# Actuator.net
KiCad netlist of a schematic drawn in EAGLE
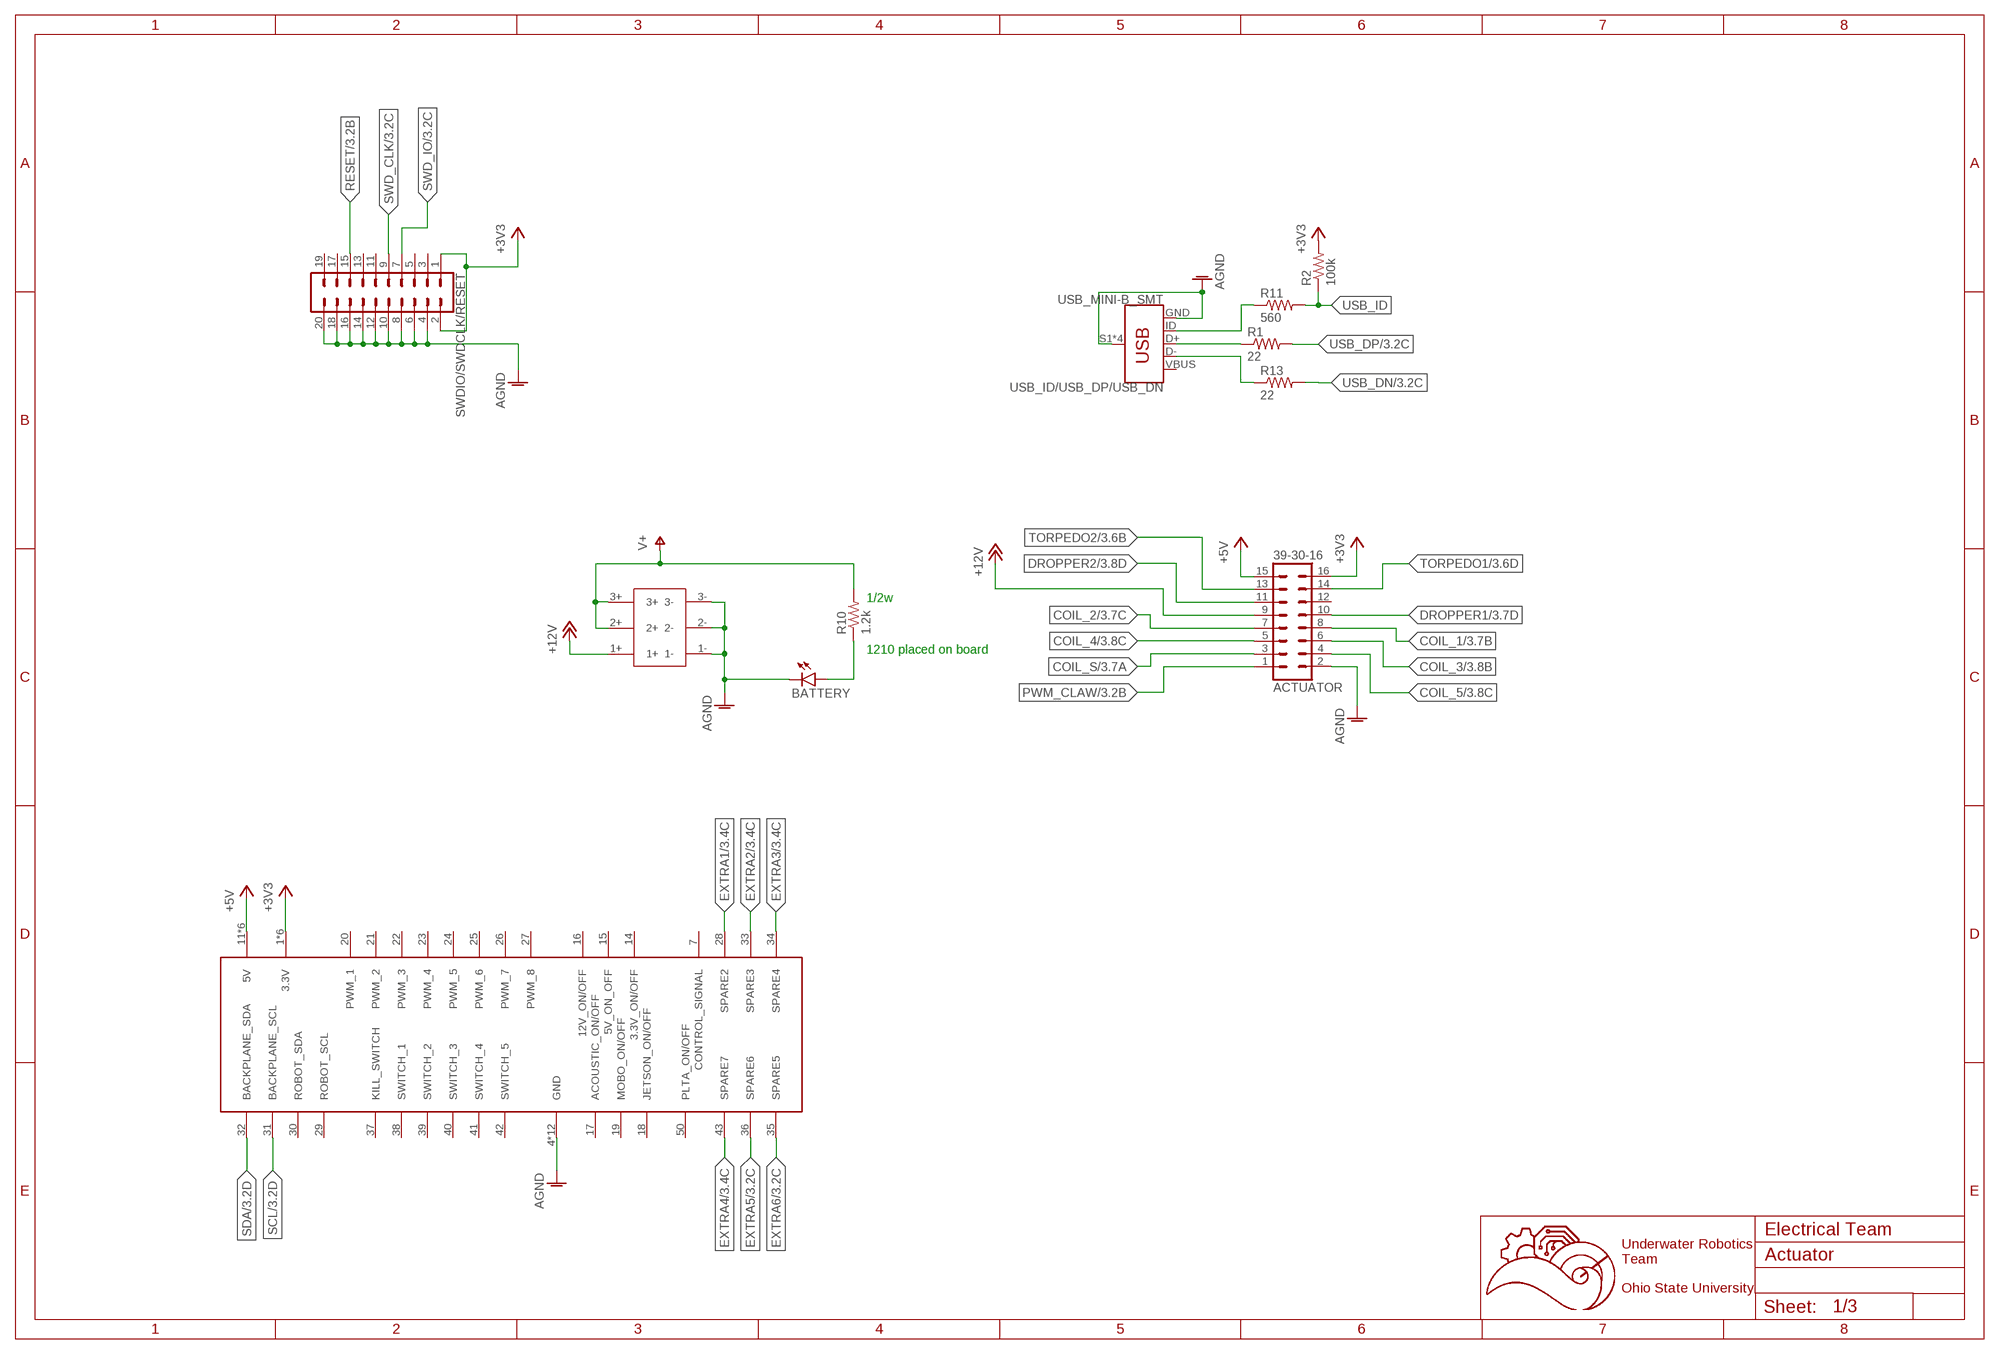
[diagram p0: schematic, sheet 1]
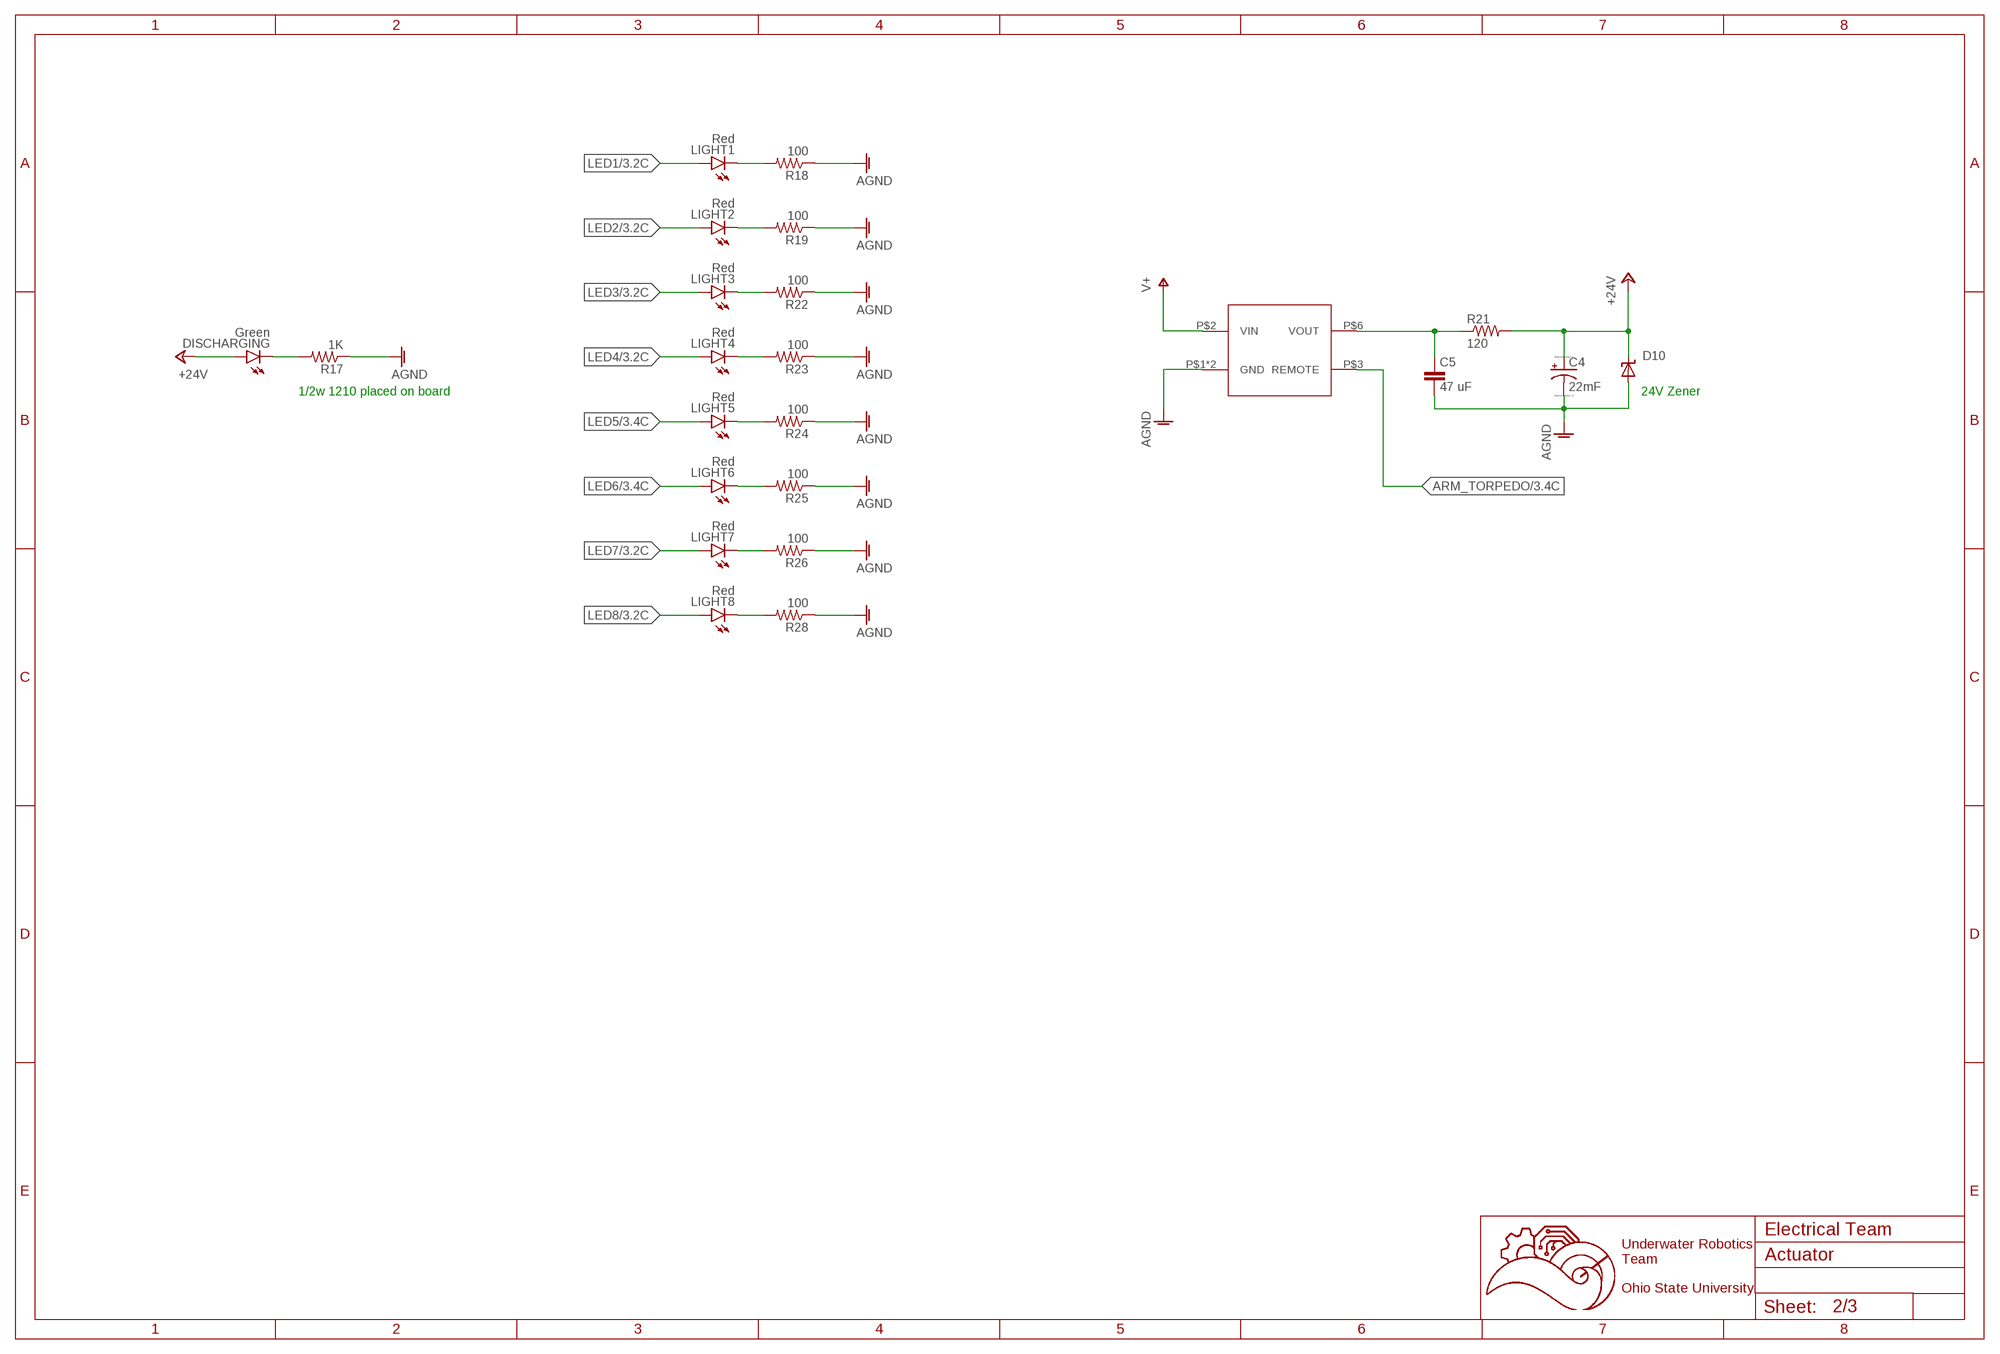
[diagram p1: schematic, sheet 2]
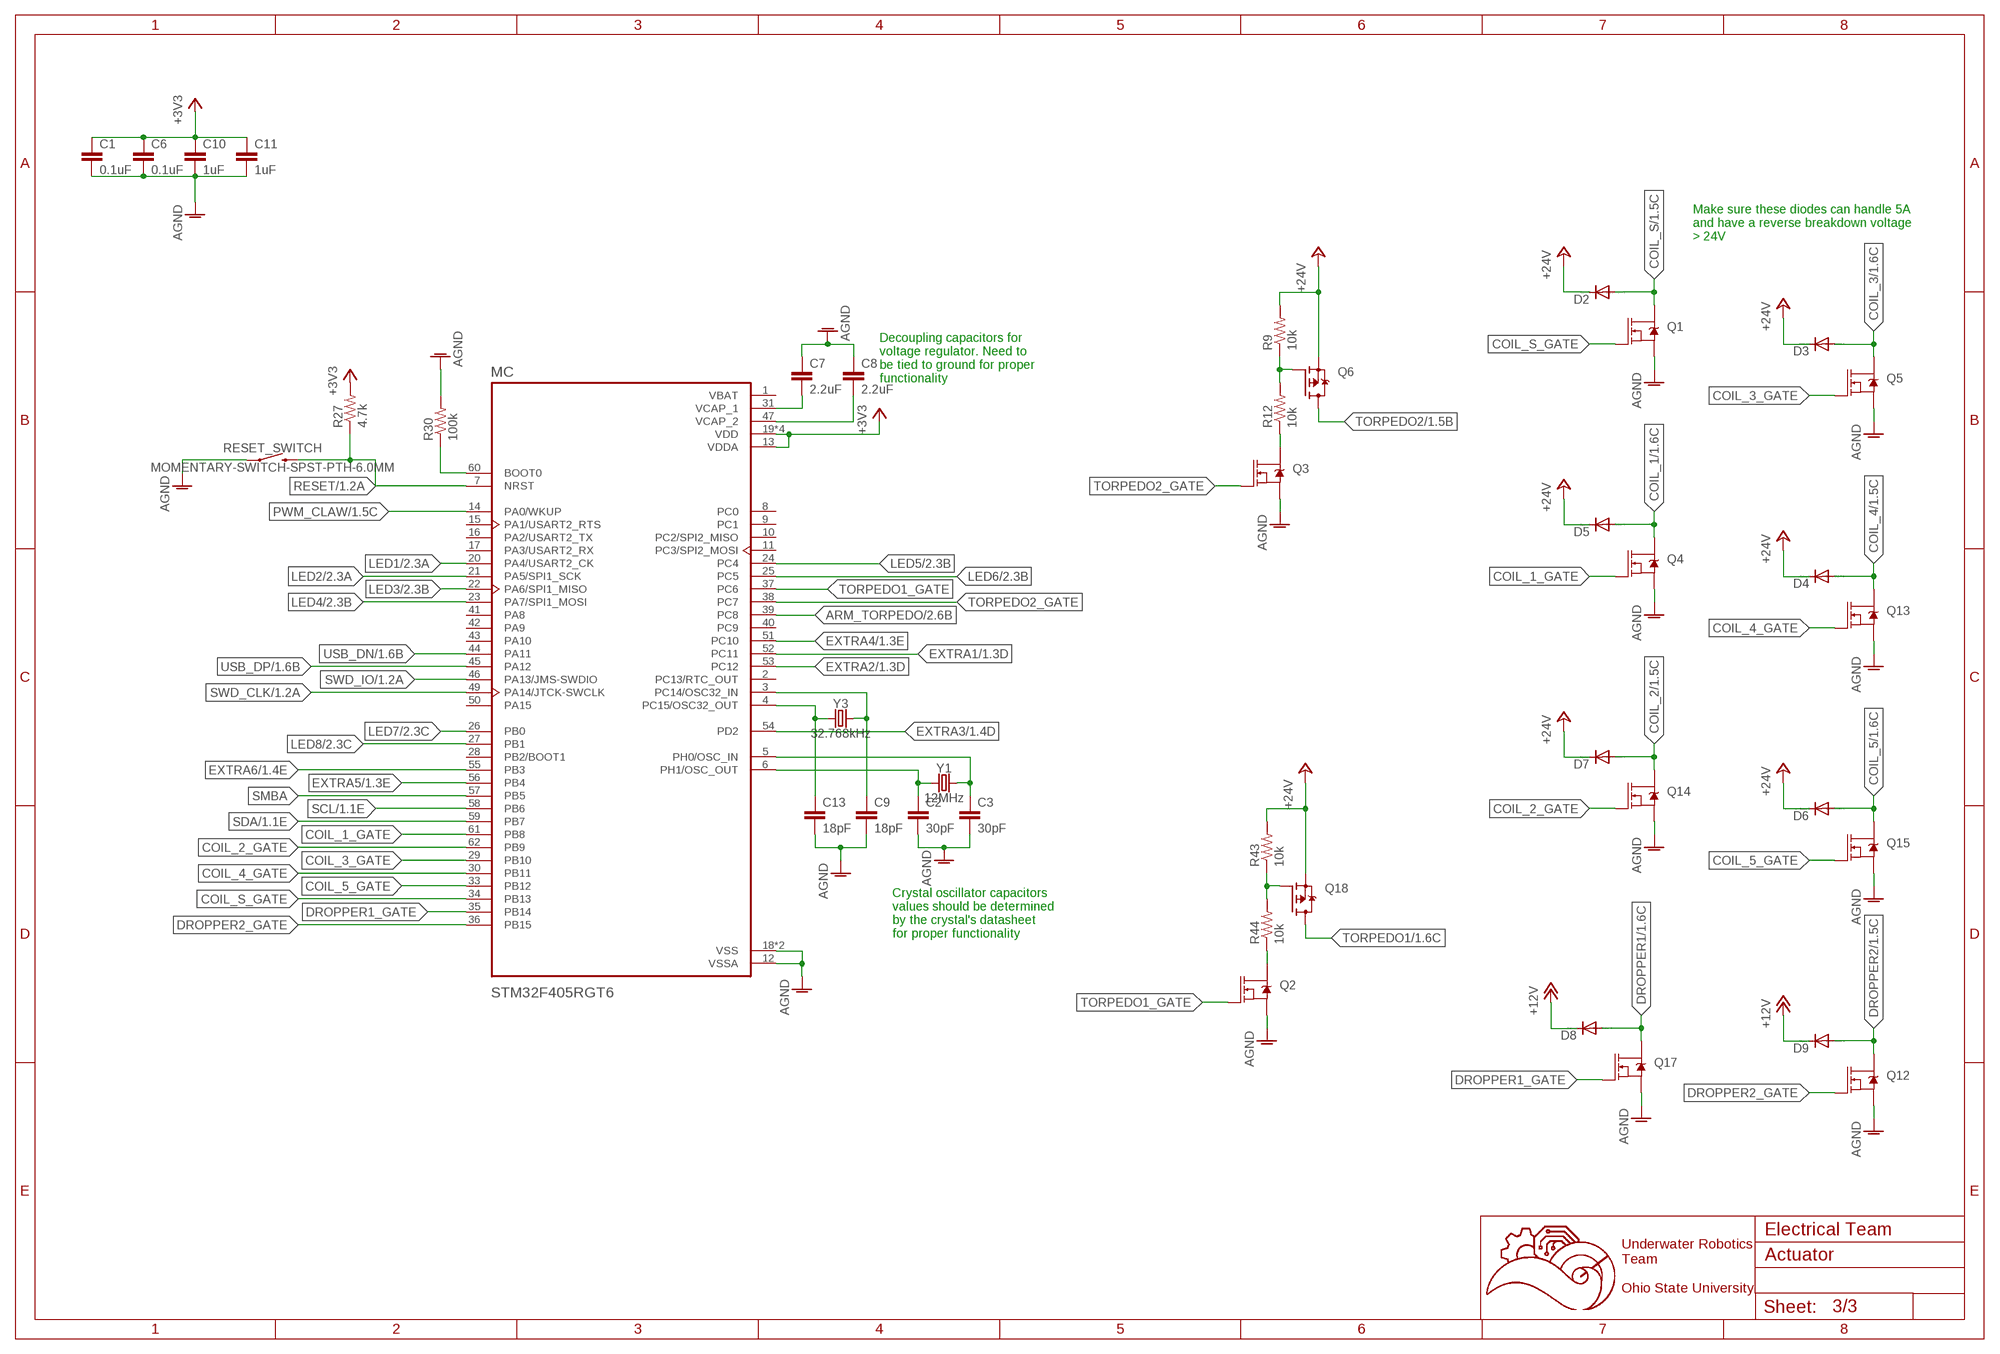
[diagram p2: schematic, sheet 3]

(export (version "E")
  (design (tool "Eeschema 10.0.6"))
  (components
    (comp (ref "C1")
      (value "0.1uF")
      (footprint "eagle-import:C0603")
      (libsource (lib "eagle-import") (part "C-EUC0603"))
    )
    (comp (ref "C2")
      (value "30pF")
      (footprint "eagle-import:C0603")
      (libsource (lib "eagle-import") (part "C-EUC0603"))
    )
    (comp (ref "C3")
      (value "30pF")
      (footprint "eagle-import:C0603")
      (libsource (lib "eagle-import") (part "C-EUC0603"))
    )
    (comp (ref "C6")
      (value "0.1uF")
      (footprint "eagle-import:C0603")
      (libsource (lib "eagle-import") (part "C-EUC0603"))
    )
    (comp (ref "C7")
      (value "2.2uF")
      (footprint "eagle-import:C0603")
      (libsource (lib "eagle-import") (part "C-EUC0603"))
    )
    (comp (ref "C8")
      (value "2.2uF")
      (footprint "eagle-import:C0603")
      (libsource (lib "eagle-import") (part "C-EUC0603"))
    )
    (comp (ref "C9")
      (value "18pF")
      (footprint "eagle-import:C0603")
      (libsource (lib "eagle-import") (part "C-EUC0603"))
    )
    (comp (ref "C10")
      (value "1uF")
      (footprint "eagle-import:C0603")
      (libsource (lib "eagle-import") (part "C-EUC0603"))
    )
    (comp (ref "C11")
      (value "1uF")
      (footprint "eagle-import:C0603")
      (libsource (lib "eagle-import") (part "C-EUC0603"))
    )
    (comp (ref "C13")
      (value "18pF")
      (footprint "eagle-import:C0603")
      (libsource (lib "eagle-import") (part "C-EUC0603"))
    )
    (comp (ref "D2")
      (value "DIODE-SMB")
      (footprint "eagle-import:SMB")
      (libsource (lib "eagle-import") (part "DIODE-SMB"))
    )
    (comp (ref "D3")
      (value "DIODE-SMB")
      (footprint "eagle-import:SMB")
      (libsource (lib "eagle-import") (part "DIODE-SMB"))
    )
    (comp (ref "D4")
      (value "DIODE-SMB")
      (footprint "eagle-import:SMB")
      (libsource (lib "eagle-import") (part "DIODE-SMB"))
    )
    (comp (ref "D5")
      (value "DIODE-SMB")
      (footprint "eagle-import:SMB")
      (libsource (lib "eagle-import") (part "DIODE-SMB"))
    )
    (comp (ref "D6")
      (value "DIODE-SMB")
      (footprint "eagle-import:SMB")
      (libsource (lib "eagle-import") (part "DIODE-SMB"))
    )
    (comp (ref "D7")
      (value "DIODE-SMB")
      (footprint "eagle-import:SMB")
      (libsource (lib "eagle-import") (part "DIODE-SMB"))
    )
    (comp (ref "D8")
      (value "DIODE-SMB")
      (footprint "eagle-import:SMB")
      (libsource (lib "eagle-import") (part "DIODE-SMB"))
    )
    (comp (ref "D9")
      (value "DIODE-SMB")
      (footprint "eagle-import:SMB")
      (libsource (lib "eagle-import") (part "DIODE-SMB"))
    )
    (comp (ref "MC")
      (value "STM32F405RGT6")
      (footprint "eagle-import:QFP50P1200X1200X160-64N")
      (fields (field (name "MF") "STMicroelectronics"))
      (libsource (lib "eagle-import") (part "STM32F405RGT6"))
    )
    (comp (ref "Q1")
      (value "MOSFET-NCH-AO3404A")
      (footprint "eagle-import:SOT23-3")
      (libsource (lib "eagle-import") (part "MOSFET-NCH-AO3404A"))
    )
    (comp (ref "Q2")
      (value "MOSFET-NCH-AO3404A")
      (footprint "eagle-import:SOT23-3")
      (libsource (lib "eagle-import") (part "MOSFET-NCH-AO3404A"))
    )
    (comp (ref "Q3")
      (value "MOSFET-NCH-AO3404A")
      (footprint "eagle-import:SOT23-3")
      (libsource (lib "eagle-import") (part "MOSFET-NCH-AO3404A"))
    )
    (comp (ref "Q4")
      (value "MOSFET-NCH-AO3404A")
      (footprint "eagle-import:SOT23-3")
      (libsource (lib "eagle-import") (part "MOSFET-NCH-AO3404A"))
    )
    (comp (ref "Q5")
      (value "MOSFET-NCH-AO3404A")
      (footprint "eagle-import:SOT23-3")
      (libsource (lib "eagle-import") (part "MOSFET-NCH-AO3404A"))
    )
    (comp (ref "Q6")
      (value "FDD4141TO252")
      (footprint "eagle-import:TO252")
      (libsource (lib "eagle-import") (part "FDD4141TO252"))
    )
    (comp (ref "Q12")
      (value "MOSFET-NCH-AO3404A")
      (footprint "eagle-import:SOT23-3")
      (libsource (lib "eagle-import") (part "MOSFET-NCH-AO3404A"))
    )
    (comp (ref "Q13")
      (value "MOSFET-NCH-AO3404A")
      (footprint "eagle-import:SOT23-3")
      (libsource (lib "eagle-import") (part "MOSFET-NCH-AO3404A"))
    )
    (comp (ref "Q14")
      (value "MOSFET-NCH-AO3404A")
      (footprint "eagle-import:SOT23-3")
      (libsource (lib "eagle-import") (part "MOSFET-NCH-AO3404A"))
    )
    (comp (ref "Q15")
      (value "MOSFET-NCH-AO3404A")
      (footprint "eagle-import:SOT23-3")
      (libsource (lib "eagle-import") (part "MOSFET-NCH-AO3404A"))
    )
    (comp (ref "Q17")
      (value "MOSFET-NCH-AO3404A")
      (footprint "eagle-import:SOT23-3")
      (libsource (lib "eagle-import") (part "MOSFET-NCH-AO3404A"))
    )
    (comp (ref "Q18")
      (value "FDD4141TO252")
      (footprint "eagle-import:TO252")
      (libsource (lib "eagle-import") (part "FDD4141TO252"))
    )
    (comp (ref "R9")
      (value "10k")
      (footprint "eagle-import:R0603")
      (libsource (lib "eagle-import") (part "resistor_348_R-US_R0603"))
    )
    (comp (ref "R12")
      (value "10k")
      (footprint "eagle-import:R0603")
      (libsource (lib "eagle-import") (part "resistor_348_R-US_R0603"))
    )
    (comp (ref "R27")
      (value "4.7k")
      (footprint "eagle-import:R0603")
      (libsource (lib "eagle-import") (part "R-US_R0603"))
    )
    (comp (ref "R30")
      (value "100k")
      (footprint "eagle-import:R0603")
      (libsource (lib "eagle-import") (part "R-US_R0603"))
    )
    (comp (ref "R43")
      (value "10k")
      (footprint "eagle-import:R0603")
      (libsource (lib "eagle-import") (part "resistor_348_R-US_R0603"))
    )
    (comp (ref "R44")
      (value "10k")
      (footprint "eagle-import:R0603")
      (libsource (lib "eagle-import") (part "resistor_348_R-US_R0603"))
    )
    (comp (ref "RESET_SWITCH")
      (value "MOMENTARY-SWITCH-SPST-PTH-6.0MM")
      (footprint "eagle-import:TACTILE_SWITCH_PTH_6.0MM")
      (libsource (lib "eagle-import") (part "MOMENTARY-SWITCH-SPST-PTH-6.0MM"))
    )
    (comp (ref "Y1")
      (value "12MHz")
      (footprint "eagle-import:HC49US")
      (libsource (lib "eagle-import") (part "CRYSTAL-16MHZPTH-HC49US"))
    )
    (comp (ref "Y3")
      (value "32.768kHz")
      (footprint "eagle-import:CRYSTAL-SMD-3.2X1.5MM")
      (libsource (lib "eagle-import") (part "CRYSTAL-32.768KHZSMD-3.2X1.5"))
    )
    (comp (ref "C4")
      (value "22mF")
      (footprint "eagle-import:EB30D")
      (libsource (lib "eagle-import") (part "CPOL-USE10-30"))
    )
    (comp (ref "C5")
      (value "47 uF")
      (footprint "eagle-import:C0603")
      (libsource (lib "eagle-import") (part "C-EUC0603"))
    )
    (comp (ref "D10")
      (value "SUPPRESSOR-SMBJ")
      (footprint "eagle-import:SMBJ")
      (libsource (lib "eagle-import") (part "SUPPRESSOR-SMBJ"))
    )
    (comp (ref "DISCHARGING")
      (value "Green")
      (footprint "eagle-import:CHIPLED_0603")
      (libsource (lib "eagle-import") (part "LEDCHIPLED_0603"))
    )
    (comp (ref "LIGHT1")
      (value "Red")
      (footprint "eagle-import:CHIPLED_0603")
      (libsource (lib "eagle-import") (part "LEDCHIPLED_0603"))
    )
    (comp (ref "LIGHT2")
      (value "Red")
      (footprint "eagle-import:CHIPLED_0603")
      (libsource (lib "eagle-import") (part "LEDCHIPLED_0603"))
    )
    (comp (ref "LIGHT3")
      (value "Red")
      (footprint "eagle-import:CHIPLED_0603")
      (libsource (lib "eagle-import") (part "LEDCHIPLED_0603"))
    )
    (comp (ref "LIGHT4")
      (value "Red")
      (footprint "eagle-import:CHIPLED_0603")
      (libsource (lib "eagle-import") (part "LEDCHIPLED_0603"))
    )
    (comp (ref "LIGHT5")
      (value "Red")
      (footprint "eagle-import:CHIPLED_0603")
      (libsource (lib "eagle-import") (part "LEDCHIPLED_0603"))
    )
    (comp (ref "LIGHT6")
      (value "Red")
      (footprint "eagle-import:CHIPLED_0603")
      (libsource (lib "eagle-import") (part "LEDCHIPLED_0603"))
    )
    (comp (ref "LIGHT7")
      (value "Red")
      (footprint "eagle-import:CHIPLED_0603")
      (libsource (lib "eagle-import") (part "LEDCHIPLED_0603"))
    )
    (comp (ref "LIGHT8")
      (value "Red")
      (footprint "eagle-import:CHIPLED_0603")
      (libsource (lib "eagle-import") (part "LEDCHIPLED_0603"))
    )
    (comp (ref "R17")
      (value "1K")
      (footprint "eagle-import:R1210")
      (libsource (lib "eagle-import") (part "R-US_R1210"))
    )
    (comp (ref "R18")
      (value "100")
      (footprint "eagle-import:R0603")
      (libsource (lib "eagle-import") (part "R-US_R0603"))
    )
    (comp (ref "R19")
      (value "100")
      (footprint "eagle-import:R0603")
      (libsource (lib "eagle-import") (part "R-US_R0603"))
    )
    (comp (ref "R21")
      (value "120")
      (footprint "eagle-import:R6332W")
      (libsource (lib "eagle-import") (part "resistor_348_R-US_R6332W"))
    )
    (comp (ref "R22")
      (value "100")
      (footprint "eagle-import:R0603")
      (libsource (lib "eagle-import") (part "R-US_R0603"))
    )
    (comp (ref "R23")
      (value "100")
      (footprint "eagle-import:R0603")
      (libsource (lib "eagle-import") (part "R-US_R0603"))
    )
    (comp (ref "R24")
      (value "100")
      (footprint "eagle-import:R0603")
      (libsource (lib "eagle-import") (part "R-US_R0603"))
    )
    (comp (ref "R25")
      (value "100")
      (footprint "eagle-import:R0603")
      (libsource (lib "eagle-import") (part "R-US_R0603"))
    )
    (comp (ref "R26")
      (value "100")
      (footprint "eagle-import:R0603")
      (libsource (lib "eagle-import") (part "R-US_R0603"))
    )
    (comp (ref "R28")
      (value "100")
      (footprint "eagle-import:R0603")
      (libsource (lib "eagle-import") (part "R-US_R0603"))
    )
    (comp (ref "U$6")
      (value "TMR6-2415")
      (footprint "eagle-import:TMR6-2415")
      (libsource (lib "eagle-import") (part "TMR6-2415"))
    )
    (comp (ref "ACTUATOR")
      (value "39-30-16")
      (footprint "eagle-import:39-30-_16_")
      (libsource (lib "eagle-import") (part "39-30-?16?"))
    )
    (comp (ref "BATTERY")
      (value "LEDCHIPLED_0603")
      (footprint "eagle-import:CHIPLED_0603")
      (libsource (lib "eagle-import") (part "LEDCHIPLED_0603"))
    )
    (comp (ref "R1")
      (value "22")
      (footprint "eagle-import:R0603")
      (libsource (lib "eagle-import") (part "R-US_R0603"))
    )
    (comp (ref "R2")
      (value "100k")
      (footprint "eagle-import:R0603")
      (libsource (lib "eagle-import") (part "R-US_R0603"))
    )
    (comp (ref "R10")
      (value "1.2k")
      (footprint "eagle-import:R1210")
      (libsource (lib "eagle-import") (part "R-US_R1210"))
    )
    (comp (ref "R11")
      (value "560")
      (footprint "eagle-import:R0603")
      (libsource (lib "eagle-import") (part "R-US_R0603"))
    )
    (comp (ref "R13")
      (value "22")
      (footprint "eagle-import:R0603")
      (libsource (lib "eagle-import") (part "R-US_R0603"))
    )
    (comp (ref "SWDIO/SWDCLK/RESET")
      (value "CONN_10X2")
      (footprint "eagle-import:2X10")
      (libsource (lib "eagle-import") (part "CONN_10X2"))
    )
    (comp (ref "U$1")
      (value "5530843-EDGE")
      (footprint "eagle-import:5530843-6-BOARDFINGERS")
      (libsource (lib "eagle-import") (part "5530843-EDGE"))
    )
    (comp (ref "U$3")
      (value "6PIN-VERT")
      (footprint "eagle-import:6PIN_VERT")
      (libsource (lib "eagle-import") (part "6PIN-VERT"))
    )
    (comp (ref "USB_ID/USB_DP/USB_DN")
      (value "USB_MINI-B_SMT")
      (footprint "eagle-import:USB-MINIB")
      (libsource (lib "eagle-import") (part "USB_MINI-B_SMT"))
    )
  )
  (nets
    (net (code "1") (name "+3V3") (class "Default")
      (node (ref "ACTUATOR") (pin "16") (pinfunction "16_16") (pintype "passive"))
      (node (ref "C1") (pin "1") (pinfunction "1_1") (pintype "passive"))
      (node (ref "C10") (pin "1") (pinfunction "1_1") (pintype "passive"))
      (node (ref "C11") (pin "1") (pinfunction "1_1") (pintype "passive"))
      (node (ref "C6") (pin "1") (pinfunction "1_1") (pintype "passive"))
      (node (ref "MC") (pin "13") (pinfunction "VDDA_13") (pintype "power_in"))
      (node (ref "MC") (pin "19") (pinfunction "VDD_19") (pintype "power_in"))
      (node (ref "MC") (pin "32") (pinfunction "VDD_32") (pintype "power_in"))
      (node (ref "MC") (pin "48") (pinfunction "VDD_48") (pintype "power_in"))
      (node (ref "MC") (pin "64") (pinfunction "VDD_64") (pintype "power_in"))
      (node (ref "R2") (pin "2") (pinfunction "2_2") (pintype "passive"))
      (node (ref "R27") (pin "2") (pinfunction "2_2") (pintype "passive"))
      (node (ref "SWDIO/SWDCLK/RESET") (pin "1") (pinfunction "1_1") (pintype "passive"))
      (node (ref "SWDIO/SWDCLK/RESET") (pin "2") (pinfunction "2_2") (pintype "passive"))
      (node (ref "U$1") (pin "1") (pinfunction "3.3V_1") (pintype "bidirectional"))
      (node (ref "U$1") (pin "2") (pinfunction "3.3V_2") (pintype "bidirectional"))
      (node (ref "U$1") (pin "3") (pinfunction "3.3V_3") (pintype "bidirectional"))
      (node (ref "U$1") (pin "54") (pinfunction "3.3V_54") (pintype "bidirectional"))
      (node (ref "U$1") (pin "55") (pinfunction "3.3V_55") (pintype "bidirectional"))
      (node (ref "U$1") (pin "56") (pinfunction "3.3V_56") (pintype "bidirectional"))
    )
    (net (code "2") (name "+5V") (class "Default")
      (node (ref "ACTUATOR") (pin "15") (pinfunction "15_15") (pintype "passive"))
      (node (ref "U$1") (pin "11") (pinfunction "5V_11") (pintype "bidirectional"))
      (node (ref "U$1") (pin "12") (pinfunction "5V_12") (pintype "bidirectional"))
      (node (ref "U$1") (pin "13") (pinfunction "5V_13") (pintype "bidirectional"))
      (node (ref "U$1") (pin "44") (pinfunction "5V_44") (pintype "bidirectional"))
      (node (ref "U$1") (pin "45") (pinfunction "5V_45") (pintype "bidirectional"))
      (node (ref "U$1") (pin "46") (pinfunction "5V_46") (pintype "bidirectional"))
    )
    (net (code "3") (name "+12V") (class "Default")
      (node (ref "ACTUATOR") (pin "9") (pinfunction "9_9") (pintype "passive"))
      (node (ref "D8") (pin "C") (pinfunction "C_C") (pintype "passive"))
      (node (ref "D9") (pin "C") (pinfunction "C_C") (pintype "passive"))
      (node (ref "U$3") (pin "1+") (pinfunction "1+_1+") (pintype "bidirectional"))
    )
    (net (code "4") (name "+24V") (class "Default")
      (node (ref "C4") (pin "+") (pinfunction "+_+") (pintype "passive"))
      (node (ref "D10") (pin "C") (pinfunction "C_C") (pintype "passive"))
      (node (ref "D2") (pin "C") (pinfunction "C_C") (pintype "passive"))
      (node (ref "D3") (pin "C") (pinfunction "C_C") (pintype "passive"))
      (node (ref "D4") (pin "C") (pinfunction "C_C") (pintype "passive"))
      (node (ref "D5") (pin "C") (pinfunction "C_C") (pintype "passive"))
      (node (ref "D6") (pin "C") (pinfunction "C_C") (pintype "passive"))
      (node (ref "D7") (pin "C") (pinfunction "C_C") (pintype "passive"))
      (node (ref "DISCHARGING") (pin "A") (pinfunction "A_A") (pintype "passive"))
      (node (ref "Q18") (pin "2") (pinfunction "S_2") (pintype "passive"))
      (node (ref "Q6") (pin "2") (pinfunction "S_2") (pintype "passive"))
      (node (ref "R21") (pin "2") (pinfunction "2_2") (pintype "passive"))
      (node (ref "R43") (pin "2") (pinfunction "2_2") (pintype "passive"))
      (node (ref "R9") (pin "2") (pinfunction "2_2") (pintype "passive"))
    )
    (net (code "5") (name "AGND") (class "Default")
      (node (ref "ACTUATOR") (pin "2") (pinfunction "2_2") (pintype "passive"))
      (node (ref "BATTERY") (pin "C") (pinfunction "C_C") (pintype "passive"))
      (node (ref "C1") (pin "2") (pinfunction "2_2") (pintype "passive"))
      (node (ref "C10") (pin "2") (pinfunction "2_2") (pintype "passive"))
      (node (ref "C11") (pin "2") (pinfunction "2_2") (pintype "passive"))
      (node (ref "C13") (pin "2") (pinfunction "2_2") (pintype "passive"))
      (node (ref "C2") (pin "2") (pinfunction "2_2") (pintype "passive"))
      (node (ref "C3") (pin "2") (pinfunction "2_2") (pintype "passive"))
      (node (ref "C4") (pin "-") (pinfunction "-_-") (pintype "passive"))
      (node (ref "C5") (pin "2") (pinfunction "2_2") (pintype "passive"))
      (node (ref "C6") (pin "2") (pinfunction "2_2") (pintype "passive"))
      (node (ref "C7") (pin "1") (pinfunction "1_1") (pintype "passive"))
      (node (ref "C8") (pin "1") (pinfunction "1_1") (pintype "passive"))
      (node (ref "C9") (pin "2") (pinfunction "2_2") (pintype "passive"))
      (node (ref "D10") (pin "A") (pinfunction "A_A") (pintype "passive"))
      (node (ref "MC") (pin "12") (pinfunction "VSSA_12") (pintype "power_in"))
      (node (ref "MC") (pin "18") (pinfunction "VSS_18") (pintype "power_in"))
      (node (ref "MC") (pin "63") (pinfunction "VSS_63") (pintype "power_in"))
      (node (ref "Q1") (pin "2") (pinfunction "S_2") (pintype "bidirectional"))
      (node (ref "Q12") (pin "2") (pinfunction "S_2") (pintype "bidirectional"))
      (node (ref "Q13") (pin "2") (pinfunction "S_2") (pintype "bidirectional"))
      (node (ref "Q14") (pin "2") (pinfunction "S_2") (pintype "bidirectional"))
      (node (ref "Q15") (pin "2") (pinfunction "S_2") (pintype "bidirectional"))
      (node (ref "Q17") (pin "2") (pinfunction "S_2") (pintype "bidirectional"))
      (node (ref "Q2") (pin "2") (pinfunction "S_2") (pintype "bidirectional"))
      (node (ref "Q3") (pin "2") (pinfunction "S_2") (pintype "bidirectional"))
      (node (ref "Q4") (pin "2") (pinfunction "S_2") (pintype "bidirectional"))
      (node (ref "Q5") (pin "2") (pinfunction "S_2") (pintype "bidirectional"))
      (node (ref "R17") (pin "1") (pinfunction "1_1") (pintype "passive"))
      (node (ref "R18") (pin "1") (pinfunction "1_1") (pintype "passive"))
      (node (ref "R19") (pin "1") (pinfunction "1_1") (pintype "passive"))
      (node (ref "R22") (pin "1") (pinfunction "1_1") (pintype "passive"))
      (node (ref "R23") (pin "1") (pinfunction "1_1") (pintype "passive"))
      (node (ref "R24") (pin "1") (pinfunction "1_1") (pintype "passive"))
      (node (ref "R25") (pin "1") (pinfunction "1_1") (pintype "passive"))
      (node (ref "R26") (pin "1") (pinfunction "1_1") (pintype "passive"))
      (node (ref "R28") (pin "1") (pinfunction "1_1") (pintype "passive"))
      (node (ref "R30") (pin "2") (pinfunction "2_2") (pintype "passive"))
      (node (ref "RESET_SWITCH") (pin "1") (pinfunction "1_1") (pintype "passive"))
      (node (ref "SWDIO/SWDCLK/RESET") (pin "10") (pinfunction "10_10") (pintype "passive"))
      (node (ref "SWDIO/SWDCLK/RESET") (pin "12") (pinfunction "12_12") (pintype "passive"))
      (node (ref "SWDIO/SWDCLK/RESET") (pin "14") (pinfunction "14_14") (pintype "passive"))
      (node (ref "SWDIO/SWDCLK/RESET") (pin "16") (pinfunction "16_16") (pintype "passive"))
      (node (ref "SWDIO/SWDCLK/RESET") (pin "18") (pinfunction "18_18") (pintype "passive"))
      (node (ref "SWDIO/SWDCLK/RESET") (pin "20") (pinfunction "20_20") (pintype "passive"))
      (node (ref "SWDIO/SWDCLK/RESET") (pin "4") (pinfunction "4_4") (pintype "passive"))
      (node (ref "SWDIO/SWDCLK/RESET") (pin "6") (pinfunction "6_6") (pintype "passive"))
      (node (ref "SWDIO/SWDCLK/RESET") (pin "8") (pinfunction "8_8") (pintype "passive"))
      (node (ref "U$1") (pin "10") (pinfunction "GND_10") (pintype "bidirectional"))
      (node (ref "U$1") (pin "4") (pinfunction "GND_4") (pintype "bidirectional"))
      (node (ref "U$1") (pin "47") (pinfunction "GND_47") (pintype "bidirectional"))
      (node (ref "U$1") (pin "48") (pinfunction "GND_48") (pintype "bidirectional"))
      (node (ref "U$1") (pin "49") (pinfunction "GND_49") (pintype "bidirectional"))
      (node (ref "U$1") (pin "5") (pinfunction "GND_5") (pintype "bidirectional"))
      (node (ref "U$1") (pin "51") (pinfunction "GND_51") (pintype "bidirectional"))
      (node (ref "U$1") (pin "52") (pinfunction "GND_52") (pintype "bidirectional"))
      (node (ref "U$1") (pin "53") (pinfunction "GND_53") (pintype "bidirectional"))
      (node (ref "U$1") (pin "6") (pinfunction "GND_6") (pintype "bidirectional"))
      (node (ref "U$1") (pin "8") (pinfunction "GND_8") (pintype "bidirectional"))
      (node (ref "U$1") (pin "9") (pinfunction "GND_9") (pintype "bidirectional"))
      (node (ref "U$3") (pin "1-") (pinfunction "1-_1-") (pintype "bidirectional"))
      (node (ref "U$3") (pin "2-") (pinfunction "2-_2-") (pintype "bidirectional"))
      (node (ref "U$3") (pin "3-") (pinfunction "3-_3-") (pintype "bidirectional"))
      (node (ref "U$6") (pin "P$1") (pinfunction "GND_P$1") (pintype "bidirectional"))
      (node (ref "U$6") (pin "P$7") (pinfunction "GND_P$7") (pintype "bidirectional"))
      (node (ref "USB_ID/USB_DP/USB_DN") (pin "GND") (pinfunction "GND_GND") (pintype "power_in"))
      (node (ref "USB_ID/USB_DP/USB_DN") (pin "S1") (pinfunction "SHIELD_S1") (pintype "bidirectional"))
      (node (ref "USB_ID/USB_DP/USB_DN") (pin "S2") (pinfunction "SHIELD_S2") (pintype "bidirectional"))
      (node (ref "USB_ID/USB_DP/USB_DN") (pin "S3") (pinfunction "SHIELD_S3") (pintype "bidirectional"))
      (node (ref "USB_ID/USB_DP/USB_DN") (pin "S4") (pinfunction "SHIELD_S4") (pintype "bidirectional"))
    )
    (net (code "6") (name "ARM_TORPEDO") (class "Default")
      (node (ref "MC") (pin "39") (pinfunction "PC8_39") (pintype "bidirectional"))
      (node (ref "U$6") (pin "P$3") (pinfunction "REMOTE_P$3") (pintype "bidirectional"))
    )
    (net (code "7") (name "COIL_1") (class "Default")
      (node (ref "ACTUATOR") (pin "8") (pinfunction "8_8") (pintype "passive"))
      (node (ref "D5") (pin "A") (pinfunction "A_A") (pintype "passive"))
      (node (ref "Q4") (pin "3") (pinfunction "D_3") (pintype "bidirectional"))
    )
    (net (code "8") (name "COIL_1_GATE") (class "Default")
      (node (ref "MC") (pin "61") (pinfunction "PB8_61") (pintype "bidirectional"))
      (node (ref "Q4") (pin "1") (pinfunction "G_1") (pintype "bidirectional"))
    )
    (net (code "9") (name "COIL_2") (class "Default")
      (node (ref "ACTUATOR") (pin "7") (pinfunction "7_7") (pintype "passive"))
      (node (ref "D7") (pin "A") (pinfunction "A_A") (pintype "passive"))
      (node (ref "Q14") (pin "3") (pinfunction "D_3") (pintype "bidirectional"))
    )
    (net (code "10") (name "COIL_2_GATE") (class "Default")
      (node (ref "MC") (pin "62") (pinfunction "PB9_62") (pintype "bidirectional"))
      (node (ref "Q14") (pin "1") (pinfunction "G_1") (pintype "bidirectional"))
    )
    (net (code "11") (name "COIL_3") (class "Default")
      (node (ref "ACTUATOR") (pin "6") (pinfunction "6_6") (pintype "passive"))
      (node (ref "D3") (pin "A") (pinfunction "A_A") (pintype "passive"))
      (node (ref "Q5") (pin "3") (pinfunction "D_3") (pintype "bidirectional"))
    )
    (net (code "12") (name "COIL_3_GATE") (class "Default")
      (node (ref "MC") (pin "29") (pinfunction "PB10_29") (pintype "bidirectional"))
      (node (ref "Q5") (pin "1") (pinfunction "G_1") (pintype "bidirectional"))
    )
    (net (code "13") (name "COIL_4") (class "Default")
      (node (ref "ACTUATOR") (pin "5") (pinfunction "5_5") (pintype "passive"))
      (node (ref "D4") (pin "A") (pinfunction "A_A") (pintype "passive"))
      (node (ref "Q13") (pin "3") (pinfunction "D_3") (pintype "bidirectional"))
    )
    (net (code "14") (name "COIL_4_GATE") (class "Default")
      (node (ref "MC") (pin "30") (pinfunction "PB11_30") (pintype "bidirectional"))
      (node (ref "Q13") (pin "1") (pinfunction "G_1") (pintype "bidirectional"))
    )
    (net (code "15") (name "COIL_5") (class "Default")
      (node (ref "ACTUATOR") (pin "4") (pinfunction "4_4") (pintype "passive"))
      (node (ref "D6") (pin "A") (pinfunction "A_A") (pintype "passive"))
      (node (ref "Q15") (pin "3") (pinfunction "D_3") (pintype "bidirectional"))
    )
    (net (code "16") (name "COIL_5_GATE") (class "Default")
      (node (ref "MC") (pin "33") (pinfunction "PB12_33") (pintype "bidirectional"))
      (node (ref "Q15") (pin "1") (pinfunction "G_1") (pintype "bidirectional"))
    )
    (net (code "17") (name "COIL_S") (class "Default")
      (node (ref "ACTUATOR") (pin "3") (pinfunction "3_3") (pintype "passive"))
      (node (ref "D2") (pin "A") (pinfunction "A_A") (pintype "passive"))
      (node (ref "Q1") (pin "3") (pinfunction "D_3") (pintype "bidirectional"))
    )
    (net (code "18") (name "COIL_S_GATE") (class "Default")
      (node (ref "MC") (pin "34") (pinfunction "PB13_34") (pintype "bidirectional"))
      (node (ref "Q1") (pin "1") (pinfunction "G_1") (pintype "bidirectional"))
    )
    (net (code "19") (name "DROPPER1") (class "Default")
      (node (ref "ACTUATOR") (pin "10") (pinfunction "10_10") (pintype "passive"))
      (node (ref "D8") (pin "A") (pinfunction "A_A") (pintype "passive"))
      (node (ref "Q17") (pin "3") (pinfunction "D_3") (pintype "bidirectional"))
    )
    (net (code "20") (name "DROPPER1_GATE") (class "Default")
      (node (ref "MC") (pin "35") (pinfunction "PB14_35") (pintype "bidirectional"))
      (node (ref "Q17") (pin "1") (pinfunction "G_1") (pintype "bidirectional"))
    )
    (net (code "21") (name "DROPPER2") (class "Default")
      (node (ref "ACTUATOR") (pin "11") (pinfunction "11_11") (pintype "passive"))
      (node (ref "D9") (pin "A") (pinfunction "A_A") (pintype "passive"))
      (node (ref "Q12") (pin "3") (pinfunction "D_3") (pintype "bidirectional"))
    )
    (net (code "22") (name "DROPPER2_GATE") (class "Default")
      (node (ref "MC") (pin "36") (pinfunction "PB15_36") (pintype "bidirectional"))
      (node (ref "Q12") (pin "1") (pinfunction "G_1") (pintype "bidirectional"))
    )
    (net (code "23") (name "EXTRA1") (class "Default")
      (node (ref "MC") (pin "52") (pinfunction "PC11_52") (pintype "bidirectional"))
      (node (ref "U$1") (pin "28") (pinfunction "SPARE2_28") (pintype "bidirectional"))
    )
    (net (code "24") (name "EXTRA2") (class "Default")
      (node (ref "MC") (pin "53") (pinfunction "PC12_53") (pintype "bidirectional"))
      (node (ref "U$1") (pin "33") (pinfunction "SPARE3_33") (pintype "bidirectional"))
    )
    (net (code "25") (name "EXTRA3") (class "Default")
      (node (ref "MC") (pin "54") (pinfunction "PD2_54") (pintype "bidirectional"))
      (node (ref "U$1") (pin "34") (pinfunction "SPARE4_34") (pintype "bidirectional"))
    )
    (net (code "26") (name "EXTRA4") (class "Default")
      (node (ref "MC") (pin "51") (pinfunction "PC10_51") (pintype "bidirectional"))
      (node (ref "U$1") (pin "43") (pinfunction "SPARE7_43") (pintype "bidirectional"))
    )
    (net (code "27") (name "EXTRA5") (class "Default")
      (node (ref "MC") (pin "56") (pinfunction "PB4_56") (pintype "bidirectional"))
      (node (ref "U$1") (pin "36") (pinfunction "SPARE6_36") (pintype "bidirectional"))
    )
    (net (code "28") (name "EXTRA6") (class "Default")
      (node (ref "MC") (pin "55") (pinfunction "PB3_55") (pintype "bidirectional"))
      (node (ref "U$1") (pin "35") (pinfunction "SPARE5_35") (pintype "bidirectional"))
    )
    (net (code "29") (name "LED1") (class "Default")
      (node (ref "LIGHT1") (pin "A") (pinfunction "A_A") (pintype "passive"))
      (node (ref "MC") (pin "20") (pinfunction "PA4/USART2_CK_20") (pintype "bidirectional"))
    )
    (net (code "30") (name "LED2") (class "Default")
      (node (ref "LIGHT2") (pin "A") (pinfunction "A_A") (pintype "passive"))
      (node (ref "MC") (pin "21") (pinfunction "PA5/SPI1_SCK_21") (pintype "bidirectional"))
    )
    (net (code "31") (name "LED3") (class "Default")
      (node (ref "LIGHT3") (pin "A") (pinfunction "A_A") (pintype "passive"))
      (node (ref "MC") (pin "22") (pinfunction "PA6/SPI1_MISO_22") (pintype "bidirectional"))
    )
    (net (code "32") (name "LED4") (class "Default")
      (node (ref "LIGHT4") (pin "A") (pinfunction "A_A") (pintype "passive"))
      (node (ref "MC") (pin "23") (pinfunction "PA7/SPI1_MOSI_23") (pintype "bidirectional"))
    )
    (net (code "33") (name "LED5") (class "Default")
      (node (ref "LIGHT5") (pin "A") (pinfunction "A_A") (pintype "passive"))
      (node (ref "MC") (pin "24") (pinfunction "PC4_24") (pintype "bidirectional"))
    )
    (net (code "34") (name "LED6") (class "Default")
      (node (ref "LIGHT6") (pin "A") (pinfunction "A_A") (pintype "passive"))
      (node (ref "MC") (pin "25") (pinfunction "PC5_25") (pintype "bidirectional"))
    )
    (net (code "35") (name "LED7") (class "Default")
      (node (ref "LIGHT7") (pin "A") (pinfunction "A_A") (pintype "passive"))
      (node (ref "MC") (pin "26") (pinfunction "PB0_26") (pintype "bidirectional"))
    )
    (net (code "36") (name "LED8") (class "Default")
      (node (ref "LIGHT8") (pin "A") (pinfunction "A_A") (pintype "passive"))
      (node (ref "MC") (pin "27") (pinfunction "PB1_27") (pintype "bidirectional"))
    )
    (net (code "37") (name "Net-(BATTERY-PadA)") (class "Default")
      (node (ref "BATTERY") (pin "A") (pinfunction "A_A") (pintype "passive"))
      (node (ref "R10") (pin "1") (pinfunction "1_1") (pintype "passive"))
    )
    (net (code "38") (name "Net-(DISCHARGING-PadC)") (class "Default")
      (node (ref "DISCHARGING") (pin "C") (pinfunction "C_C") (pintype "passive"))
      (node (ref "R17") (pin "2") (pinfunction "2_2") (pintype "passive"))
    )
    (net (code "39") (name "Net-(LIGHT1-PadC)") (class "Default")
      (node (ref "LIGHT1") (pin "C") (pinfunction "C_C") (pintype "passive"))
      (node (ref "R18") (pin "2") (pinfunction "2_2") (pintype "passive"))
    )
    (net (code "40") (name "Net-(LIGHT2-PadC)") (class "Default")
      (node (ref "LIGHT2") (pin "C") (pinfunction "C_C") (pintype "passive"))
      (node (ref "R19") (pin "2") (pinfunction "2_2") (pintype "passive"))
    )
    (net (code "41") (name "Net-(LIGHT3-PadC)") (class "Default")
      (node (ref "LIGHT3") (pin "C") (pinfunction "C_C") (pintype "passive"))
      (node (ref "R22") (pin "2") (pinfunction "2_2") (pintype "passive"))
    )
    (net (code "42") (name "Net-(LIGHT4-PadC)") (class "Default")
      (node (ref "LIGHT4") (pin "C") (pinfunction "C_C") (pintype "passive"))
      (node (ref "R23") (pin "2") (pinfunction "2_2") (pintype "passive"))
    )
    (net (code "43") (name "Net-(LIGHT5-PadC)") (class "Default")
      (node (ref "LIGHT5") (pin "C") (pinfunction "C_C") (pintype "passive"))
      (node (ref "R24") (pin "2") (pinfunction "2_2") (pintype "passive"))
    )
    (net (code "44") (name "Net-(LIGHT6-PadC)") (class "Default")
      (node (ref "LIGHT6") (pin "C") (pinfunction "C_C") (pintype "passive"))
      (node (ref "R25") (pin "2") (pinfunction "2_2") (pintype "passive"))
    )
    (net (code "45") (name "Net-(LIGHT7-PadC)") (class "Default")
      (node (ref "LIGHT7") (pin "C") (pinfunction "C_C") (pintype "passive"))
      (node (ref "R26") (pin "2") (pinfunction "2_2") (pintype "passive"))
    )
    (net (code "46") (name "Net-(LIGHT8-PadC)") (class "Default")
      (node (ref "LIGHT8") (pin "C") (pinfunction "C_C") (pintype "passive"))
      (node (ref "R28") (pin "2") (pinfunction "2_2") (pintype "passive"))
    )
    (net (code "47") (name "Net-(MC-BOOT0)") (class "Default")
      (node (ref "MC") (pin "60") (pinfunction "BOOT0_60") (pintype "bidirectional"))
      (node (ref "R30") (pin "1") (pinfunction "1_1") (pintype "passive"))
    )
    (net (code "48") (name "Net-(MC-PC14{slash}OSC32_IN)") (class "Default")
      (node (ref "C9") (pin "1") (pinfunction "1_1") (pintype "passive"))
      (node (ref "MC") (pin "3") (pinfunction "PC14/OSC32_IN_3") (pintype "bidirectional"))
      (node (ref "Y3") (pin "P$2") (pinfunction "2_P$2") (pintype "passive"))
    )
    (net (code "49") (name "Net-(MC-PC15{slash}OSC32_OUT)") (class "Default")
      (node (ref "C13") (pin "1") (pinfunction "1_1") (pintype "passive"))
      (node (ref "MC") (pin "4") (pinfunction "PC15/OSC32_OUT_4") (pintype "bidirectional"))
      (node (ref "Y3") (pin "P$1") (pinfunction "1_P$1") (pintype "passive"))
    )
    (net (code "50") (name "Net-(MC-PH0{slash}OSC_IN)") (class "Default")
      (node (ref "C3") (pin "1") (pinfunction "1_1") (pintype "passive"))
      (node (ref "MC") (pin "5") (pinfunction "PH0/OSC_IN_5") (pintype "bidirectional"))
      (node (ref "Y1") (pin "2") (pinfunction "2_2") (pintype "passive"))
    )
    (net (code "51") (name "Net-(MC-PH1{slash}OSC_OUT)") (class "Default")
      (node (ref "C2") (pin "1") (pinfunction "1_1") (pintype "passive"))
      (node (ref "MC") (pin "6") (pinfunction "PH1/OSC_OUT_6") (pintype "bidirectional"))
      (node (ref "Y1") (pin "1") (pinfunction "1_1") (pintype "passive"))
    )
    (net (code "52") (name "Net-(MC-VCAP_1)") (class "Default")
      (node (ref "C7") (pin "2") (pinfunction "2_2") (pintype "passive"))
      (node (ref "MC") (pin "31") (pinfunction "VCAP_1_31") (pintype "power_in"))
    )
    (net (code "53") (name "Net-(MC-VCAP_2)") (class "Default")
      (node (ref "C8") (pin "2") (pinfunction "2_2") (pintype "passive"))
      (node (ref "MC") (pin "47") (pinfunction "VCAP_2_47") (pintype "power_in"))
    )
    (net (code "54") (name "Net-(Q2-D)") (class "Default")
      (node (ref "Q2") (pin "3") (pinfunction "D_3") (pintype "bidirectional"))
      (node (ref "R44") (pin "1") (pinfunction "1_1") (pintype "passive"))
    )
    (net (code "55") (name "Net-(Q3-D)") (class "Default")
      (node (ref "Q3") (pin "3") (pinfunction "D_3") (pintype "bidirectional"))
      (node (ref "R12") (pin "1") (pinfunction "1_1") (pintype "passive"))
    )
    (net (code "56") (name "Net-(Q6-G)") (class "Default")
      (node (ref "Q6") (pin "1") (pinfunction "G_1") (pintype "passive"))
      (node (ref "R12") (pin "2") (pinfunction "2_2") (pintype "passive"))
      (node (ref "R9") (pin "1") (pinfunction "1_1") (pintype "passive"))
    )
    (net (code "57") (name "Net-(Q18-G)") (class "Default")
      (node (ref "Q18") (pin "1") (pinfunction "G_1") (pintype "passive"))
      (node (ref "R43") (pin "1") (pinfunction "1_1") (pintype "passive"))
      (node (ref "R44") (pin "2") (pinfunction "2_2") (pintype "passive"))
    )
    (net (code "58") (name "Net-(R1-Pad1)") (class "Default")
      (node (ref "R1") (pin "1") (pinfunction "1_1") (pintype "passive"))
      (node (ref "USB_ID/USB_DP/USB_DN") (pin "D+") (pinfunction "D+_D+") (pintype "bidirectional"))
    )
    (net (code "59") (name "Net-(R11-Pad1)") (class "Default")
      (node (ref "R11") (pin "1") (pinfunction "1_1") (pintype "passive"))
      (node (ref "USB_ID/USB_DP/USB_DN") (pin "ID") (pinfunction "ID_ID") (pintype "bidirectional"))
    )
    (net (code "60") (name "Net-(R13-Pad1)") (class "Default")
      (node (ref "R13") (pin "1") (pinfunction "1_1") (pintype "passive"))
      (node (ref "USB_ID/USB_DP/USB_DN") (pin "D-") (pinfunction "D-_D-") (pintype "bidirectional"))
    )
    (net (code "61") (name "Net-(U$6-VOUT)") (class "Default")
      (node (ref "C5") (pin "1") (pinfunction "1_1") (pintype "passive"))
      (node (ref "R21") (pin "1") (pinfunction "1_1") (pintype "passive"))
      (node (ref "U$6") (pin "P$6") (pinfunction "VOUT_P$6") (pintype "bidirectional"))
    )
    (net (code "62") (name "PWM_CLAW") (class "Default")
      (node (ref "ACTUATOR") (pin "1") (pinfunction "1_1") (pintype "passive"))
      (node (ref "MC") (pin "14") (pinfunction "PA0/WKUP_14") (pintype "bidirectional"))
    )
    (net (code "63") (name "RESET") (class "Default")
      (node (ref "MC") (pin "7") (pinfunction "NRST_7") (pintype "bidirectional"))
      (node (ref "R27") (pin "1") (pinfunction "1_1") (pintype "passive"))
      (node (ref "RESET_SWITCH") (pin "3") (pinfunction "2_3") (pintype "passive"))
      (node (ref "SWDIO/SWDCLK/RESET") (pin "15") (pinfunction "15_15") (pintype "passive"))
    )
    (net (code "64") (name "SCL") (class "Default")
      (node (ref "MC") (pin "58") (pinfunction "PB6_58") (pintype "bidirectional"))
      (node (ref "U$1") (pin "31") (pinfunction "BACKPLANE_SCL_31") (pintype "bidirectional"))
    )
    (net (code "65") (name "SDA") (class "Default")
      (node (ref "MC") (pin "59") (pinfunction "PB7_59") (pintype "bidirectional"))
      (node (ref "U$1") (pin "32") (pinfunction "BACKPLANE_SDA_32") (pintype "bidirectional"))
    )
    (net (code "66") (name "SMBA") (class "Default")
      (node (ref "MC") (pin "57") (pinfunction "PB5_57") (pintype "bidirectional"))
    )
    (net (code "67") (name "SWD_CLK") (class "Default")
      (node (ref "MC") (pin "49") (pinfunction "PA14/JTCK-SWCLK_49") (pintype "bidirectional"))
      (node (ref "SWDIO/SWDCLK/RESET") (pin "9") (pinfunction "9_9") (pintype "passive"))
    )
    (net (code "68") (name "SWD_IO") (class "Default")
      (node (ref "MC") (pin "46") (pinfunction "PA13/JMS-SWDIO_46") (pintype "bidirectional"))
      (node (ref "SWDIO/SWDCLK/RESET") (pin "7") (pinfunction "7_7") (pintype "passive"))
    )
    (net (code "69") (name "TORPEDO1") (class "Default")
      (node (ref "ACTUATOR") (pin "14") (pinfunction "14_14") (pintype "passive"))
      (node (ref "Q18") (pin "3") (pinfunction "D_3") (pintype "passive"))
    )
    (net (code "70") (name "TORPEDO1_GATE") (class "Default")
      (node (ref "MC") (pin "37") (pinfunction "PC6_37") (pintype "bidirectional"))
      (node (ref "Q2") (pin "1") (pinfunction "G_1") (pintype "bidirectional"))
    )
    (net (code "71") (name "TORPEDO2") (class "Default")
      (node (ref "ACTUATOR") (pin "13") (pinfunction "13_13") (pintype "passive"))
      (node (ref "Q6") (pin "3") (pinfunction "D_3") (pintype "passive"))
    )
    (net (code "72") (name "TORPEDO2_GATE") (class "Default")
      (node (ref "MC") (pin "38") (pinfunction "PC7_38") (pintype "bidirectional"))
      (node (ref "Q3") (pin "1") (pinfunction "G_1") (pintype "bidirectional"))
    )
    (net (code "73") (name "USB_DN") (class "Default")
      (node (ref "MC") (pin "44") (pinfunction "PA11_44") (pintype "bidirectional"))
      (node (ref "R13") (pin "2") (pinfunction "2_2") (pintype "passive"))
    )
    (net (code "74") (name "USB_DP") (class "Default")
      (node (ref "MC") (pin "45") (pinfunction "PA12_45") (pintype "bidirectional"))
      (node (ref "R1") (pin "2") (pinfunction "2_2") (pintype "passive"))
    )
    (net (code "75") (name "USB_ID") (class "Default")
      (node (ref "R11") (pin "2") (pinfunction "2_2") (pintype "passive"))
      (node (ref "R2") (pin "1") (pinfunction "1_1") (pintype "passive"))
    )
    (net (code "76") (name "V+") (class "Default")
      (node (ref "R10") (pin "2") (pinfunction "2_2") (pintype "passive"))
      (node (ref "U$3") (pin "2+") (pinfunction "2+_2+") (pintype "bidirectional"))
      (node (ref "U$3") (pin "3+") (pinfunction "3+_3+") (pintype "bidirectional"))
      (node (ref "U$6") (pin "P$2") (pinfunction "VIN_P$2") (pintype "bidirectional"))
    )
    (net (code "77") (name "VBAT") (class "Default")
      (node (ref "MC") (pin "1") (pinfunction "VBAT_1") (pintype "power_in"))
    )
    (net (code "78") (name "VBUS") (class "Default")
      (node (ref "USB_ID/USB_DP/USB_DN") (pin "VBUS") (pinfunction "VBUS_VBUS") (pintype "power_in"))
    )
    (net (code "79") (name "unconnected-(ACTUATOR-Pad12)") (class "Default")
      (node (ref "ACTUATOR") (pin "12") (pinfunction "12_12") (pintype "passive"))
    )
    (net (code "80") (name "unconnected-(MC-PA1{slash}USART2_RTS-Pad15)") (class "Default")
      (node (ref "MC") (pin "15") (pinfunction "PA1/USART2_RTS_15") (pintype "bidirectional"))
    )
    (net (code "81") (name "unconnected-(MC-PA2{slash}USART2_TX-Pad16)") (class "Default")
      (node (ref "MC") (pin "16") (pinfunction "PA2/USART2_TX_16") (pintype "bidirectional"))
    )
    (net (code "82") (name "unconnected-(MC-PA3{slash}USART2_RX-Pad17)") (class "Default")
      (node (ref "MC") (pin "17") (pinfunction "PA3/USART2_RX_17") (pintype "bidirectional"))
    )
    (net (code "83") (name "unconnected-(MC-PA8-Pad41)") (class "Default")
      (node (ref "MC") (pin "41") (pinfunction "PA8_41") (pintype "bidirectional"))
    )
    (net (code "84") (name "unconnected-(MC-PA9-Pad42)") (class "Default")
      (node (ref "MC") (pin "42") (pinfunction "PA9_42") (pintype "bidirectional"))
    )
    (net (code "85") (name "unconnected-(MC-PA10-Pad43)") (class "Default")
      (node (ref "MC") (pin "43") (pinfunction "PA10_43") (pintype "bidirectional"))
    )
    (net (code "86") (name "unconnected-(MC-PA15-Pad50)") (class "Default")
      (node (ref "MC") (pin "50") (pinfunction "PA15_50") (pintype "bidirectional"))
    )
    (net (code "87") (name "unconnected-(MC-PB2{slash}BOOT1-Pad28)") (class "Default")
      (node (ref "MC") (pin "28") (pinfunction "PB2/BOOT1_28") (pintype "bidirectional"))
    )
    (net (code "88") (name "unconnected-(MC-PC0-Pad8)") (class "Default")
      (node (ref "MC") (pin "8") (pinfunction "PC0_8") (pintype "bidirectional"))
    )
    (net (code "89") (name "unconnected-(MC-PC1-Pad9)") (class "Default")
      (node (ref "MC") (pin "9") (pinfunction "PC1_9") (pintype "bidirectional"))
    )
    (net (code "90") (name "unconnected-(MC-PC2{slash}SPI2_MISO-Pad10)") (class "Default")
      (node (ref "MC") (pin "10") (pinfunction "PC2/SPI2_MISO_10") (pintype "bidirectional"))
    )
    (net (code "91") (name "unconnected-(MC-PC3{slash}SPI2_MOSI-Pad11)") (class "Default")
      (node (ref "MC") (pin "11") (pinfunction "PC3/SPI2_MOSI_11") (pintype "bidirectional"))
    )
    (net (code "92") (name "unconnected-(MC-PC9-Pad40)") (class "Default")
      (node (ref "MC") (pin "40") (pinfunction "PC9_40") (pintype "bidirectional"))
    )
    (net (code "93") (name "unconnected-(MC-PC13{slash}RTC_OUT-Pad2)") (class "Default")
      (node (ref "MC") (pin "2") (pinfunction "PC13/RTC_OUT_2") (pintype "bidirectional"))
    )
    (net (code "94") (name "unconnected-(SWDIO/SWDCLK/RESET-Pad3)") (class "Default")
      (node (ref "SWDIO/SWDCLK/RESET") (pin "3") (pinfunction "3_3") (pintype "passive"))
    )
    (net (code "95") (name "unconnected-(SWDIO/SWDCLK/RESET-Pad5)") (class "Default")
      (node (ref "SWDIO/SWDCLK/RESET") (pin "5") (pinfunction "5_5") (pintype "passive"))
    )
    (net (code "96") (name "unconnected-(SWDIO/SWDCLK/RESET-Pad11)") (class "Default")
      (node (ref "SWDIO/SWDCLK/RESET") (pin "11") (pinfunction "11_11") (pintype "passive"))
    )
    (net (code "97") (name "unconnected-(SWDIO/SWDCLK/RESET-Pad13)") (class "Default")
      (node (ref "SWDIO/SWDCLK/RESET") (pin "13") (pinfunction "13_13") (pintype "passive"))
    )
    (net (code "98") (name "unconnected-(SWDIO/SWDCLK/RESET-Pad17)") (class "Default")
      (node (ref "SWDIO/SWDCLK/RESET") (pin "17") (pinfunction "17_17") (pintype "passive"))
    )
    (net (code "99") (name "unconnected-(SWDIO/SWDCLK/RESET-Pad19)") (class "Default")
      (node (ref "SWDIO/SWDCLK/RESET") (pin "19") (pinfunction "19_19") (pintype "passive"))
    )
    (net (code "100") (name "unconnected-(U$1-3.3V_ON{slash}OFF-Pad14)") (class "Default")
      (node (ref "U$1") (pin "14") (pinfunction "3.3V_ON/OFF_14") (pintype "bidirectional"))
    )
    (net (code "101") (name "unconnected-(U$1-5V_ON_OFF-Pad15)") (class "Default")
      (node (ref "U$1") (pin "15") (pinfunction "5V_ON_OFF_15") (pintype "bidirectional"))
    )
    (net (code "102") (name "unconnected-(U$1-12V_ON{slash}OFF-Pad16)") (class "Default")
      (node (ref "U$1") (pin "16") (pinfunction "12V_ON/OFF_16") (pintype "bidirectional"))
    )
    (net (code "103") (name "unconnected-(U$1-ACOUSTIC_ON{slash}OFF-Pad17)") (class "Default")
      (node (ref "U$1") (pin "17") (pinfunction "ACOUSTIC_ON/OFF_17") (pintype "bidirectional"))
    )
    (net (code "104") (name "unconnected-(U$1-CONTROL_SIGNAL-Pad7)") (class "Default")
      (node (ref "U$1") (pin "7") (pinfunction "CONTROL_SIGNAL_7") (pintype "bidirectional"))
    )
    (net (code "105") (name "unconnected-(U$1-JETSON_ON{slash}OFF-Pad18)") (class "Default")
      (node (ref "U$1") (pin "18") (pinfunction "JETSON_ON/OFF_18") (pintype "bidirectional"))
    )
    (net (code "106") (name "unconnected-(U$1-KILL_SWITCH-Pad37)") (class "Default")
      (node (ref "U$1") (pin "37") (pinfunction "KILL_SWITCH_37") (pintype "output"))
    )
    (net (code "107") (name "unconnected-(U$1-MOBO_ON{slash}OFF-Pad19)") (class "Default")
      (node (ref "U$1") (pin "19") (pinfunction "MOBO_ON/OFF_19") (pintype "bidirectional"))
    )
    (net (code "108") (name "unconnected-(U$1-PLTA_ON{slash}OFF-Pad50)") (class "Default")
      (node (ref "U$1") (pin "50") (pinfunction "PLTA_ON/OFF_50") (pintype "bidirectional"))
    )
    (net (code "109") (name "unconnected-(U$1-PWM_1-Pad20)") (class "Default")
      (node (ref "U$1") (pin "20") (pinfunction "PWM_1_20") (pintype "bidirectional"))
    )
    (net (code "110") (name "unconnected-(U$1-PWM_2-Pad21)") (class "Default")
      (node (ref "U$1") (pin "21") (pinfunction "PWM_2_21") (pintype "bidirectional"))
    )
    (net (code "111") (name "unconnected-(U$1-PWM_3-Pad22)") (class "Default")
      (node (ref "U$1") (pin "22") (pinfunction "PWM_3_22") (pintype "bidirectional"))
    )
    (net (code "112") (name "unconnected-(U$1-PWM_4-Pad23)") (class "Default")
      (node (ref "U$1") (pin "23") (pinfunction "PWM_4_23") (pintype "bidirectional"))
    )
    (net (code "113") (name "unconnected-(U$1-PWM_5-Pad24)") (class "Default")
      (node (ref "U$1") (pin "24") (pinfunction "PWM_5_24") (pintype "bidirectional"))
    )
    (net (code "114") (name "unconnected-(U$1-PWM_6-Pad25)") (class "Default")
      (node (ref "U$1") (pin "25") (pinfunction "PWM_6_25") (pintype "bidirectional"))
    )
    (net (code "115") (name "unconnected-(U$1-PWM_7-Pad26)") (class "Default")
      (node (ref "U$1") (pin "26") (pinfunction "PWM_7_26") (pintype "bidirectional"))
    )
    (net (code "116") (name "unconnected-(U$1-PWM_8-Pad27)") (class "Default")
      (node (ref "U$1") (pin "27") (pinfunction "PWM_8_27") (pintype "bidirectional"))
    )
    (net (code "117") (name "unconnected-(U$1-ROBOT_SCL-Pad29)") (class "Default")
      (node (ref "U$1") (pin "29") (pinfunction "ROBOT_SCL_29") (pintype "bidirectional"))
    )
    (net (code "118") (name "unconnected-(U$1-ROBOT_SDA-Pad30)") (class "Default")
      (node (ref "U$1") (pin "30") (pinfunction "ROBOT_SDA_30") (pintype "bidirectional"))
    )
    (net (code "119") (name "unconnected-(U$1-SWITCH_1-Pad38)") (class "Default")
      (node (ref "U$1") (pin "38") (pinfunction "SWITCH_1_38") (pintype "output"))
    )
    (net (code "120") (name "unconnected-(U$1-SWITCH_2-Pad39)") (class "Default")
      (node (ref "U$1") (pin "39") (pinfunction "SWITCH_2_39") (pintype "output"))
    )
    (net (code "121") (name "unconnected-(U$1-SWITCH_3-Pad40)") (class "Default")
      (node (ref "U$1") (pin "40") (pinfunction "SWITCH_3_40") (pintype "output"))
    )
    (net (code "122") (name "unconnected-(U$1-SWITCH_4-Pad41)") (class "Default")
      (node (ref "U$1") (pin "41") (pinfunction "SWITCH_4_41") (pintype "output"))
    )
    (net (code "123") (name "unconnected-(U$1-SWITCH_5-Pad42)") (class "Default")
      (node (ref "U$1") (pin "42") (pinfunction "SWITCH_5_42") (pintype "output"))
    )
  )
)
